# EVE_v0-3.net
KiCad netlist of a schematic drawn in EAGLE
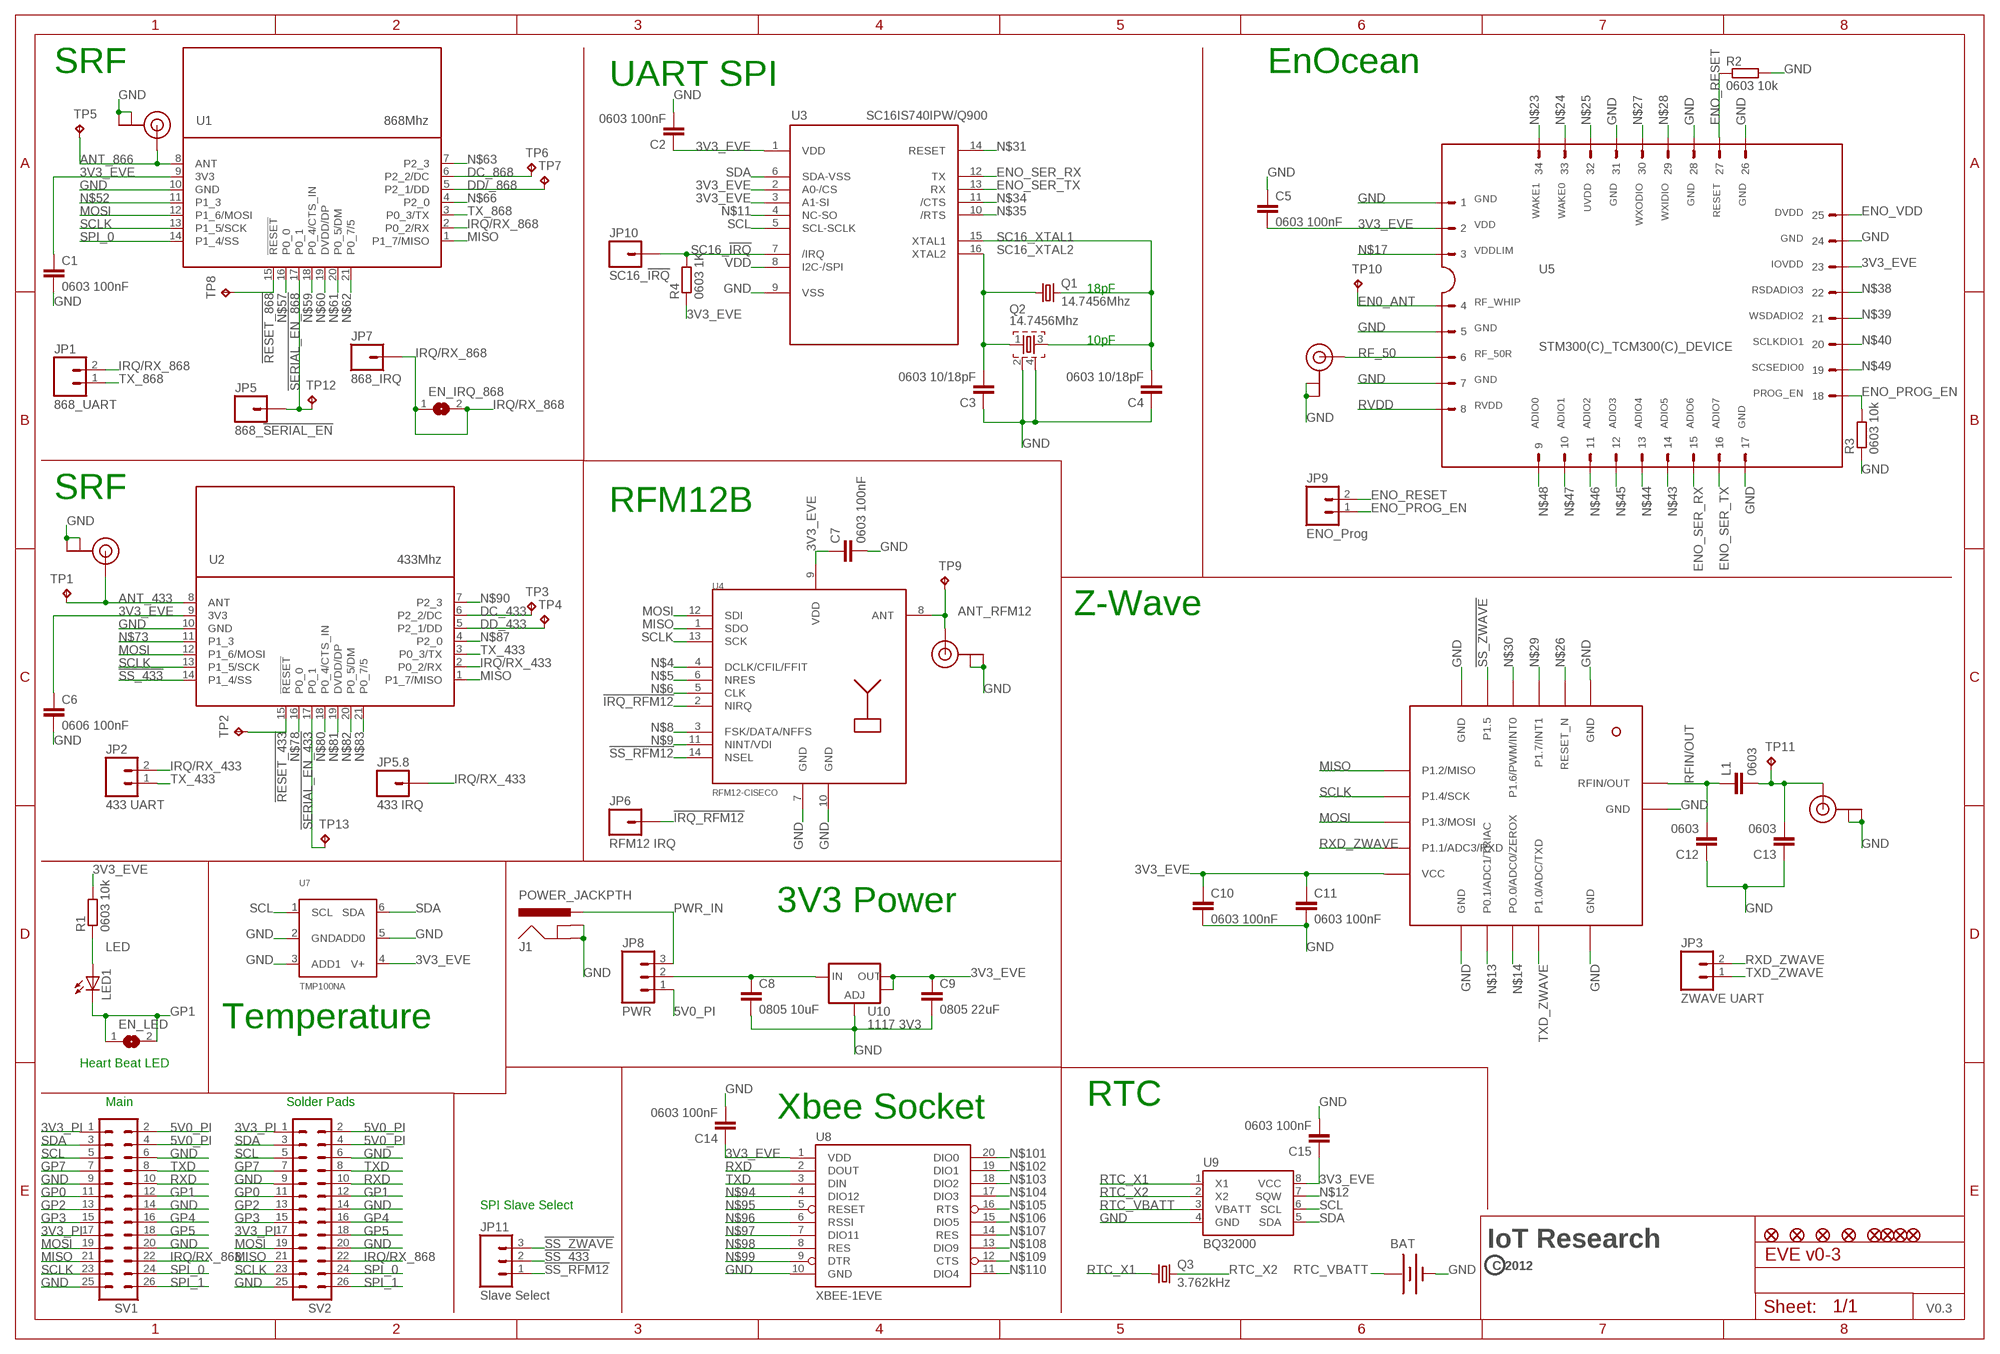
[diagram p0: schematic, sheet 1]

(export (version "E")
  (design (tool "Eeschema 10.0.6"))
  (components
    (comp (ref "BAT")
      (value "BATTERY12MM-BK-855")
      (footprint "eagle-import:BATTCON_12MM-BK-885")
      (libsource (lib "eagle-import") (part "BATTERY12MM-BK-855"))
    )
    (comp (ref "C1")
      (value "0603 100nF")
      (footprint "eagle-import:C0603K-SMALL")
      (libsource (lib "eagle-import") (part "C-EUC0603K-SMALL"))
    )
    (comp (ref "C2")
      (value "0603 100nF")
      (footprint "eagle-import:C0603K-SMALL")
      (libsource (lib "eagle-import") (part "C-EUC0603K-SMALL"))
    )
    (comp (ref "C3")
      (value "0603 10/18pF")
      (footprint "eagle-import:C0603K-SMALL")
      (libsource (lib "eagle-import") (part "C-EUC0603K-SMALL"))
    )
    (comp (ref "C4")
      (value "0603 10/18pF")
      (footprint "eagle-import:C0603K-SMALL")
      (libsource (lib "eagle-import") (part "C-EUC0603K-SMALL"))
    )
    (comp (ref "C5")
      (value "0603 100nF")
      (footprint "eagle-import:C0603K-SMALL")
      (libsource (lib "eagle-import") (part "C-EUC0603K-SMALL"))
    )
    (comp (ref "C6")
      (value "0606 100nF")
      (footprint "eagle-import:C0603K-SMALL")
      (libsource (lib "eagle-import") (part "C-EUC0603K-SMALL"))
    )
    (comp (ref "C7")
      (value "0603 100nF")
      (footprint "eagle-import:C0603K-SMALL")
      (libsource (lib "eagle-import") (part "C-EUC0603K-SMALL"))
    )
    (comp (ref "C8")
      (value "0805 10uF")
      (footprint "eagle-import:C0805")
      (libsource (lib "eagle-import") (part "C-EUC0805"))
    )
    (comp (ref "C9")
      (value "0805 22uF")
      (footprint "eagle-import:C0805")
      (libsource (lib "eagle-import") (part "C-EUC0805"))
    )
    (comp (ref "C10")
      (value "0603 100nF")
      (footprint "eagle-import:C0603K-SMALL")
      (libsource (lib "eagle-import") (part "C-EUC0603K-SMALL"))
    )
    (comp (ref "C11")
      (value "0603 100nF")
      (footprint "eagle-import:C0603K-SMALL")
      (libsource (lib "eagle-import") (part "C-EUC0603K-SMALL"))
    )
    (comp (ref "C12")
      (value "0603")
      (footprint "eagle-import:C0603K-SMALL")
      (libsource (lib "eagle-import") (part "C-EUC0603K-SMALL"))
    )
    (comp (ref "C13")
      (value "0603")
      (footprint "eagle-import:C0603K-SMALL")
      (libsource (lib "eagle-import") (part "C-EUC0603K-SMALL"))
    )
    (comp (ref "C14")
      (value "0603 100nF")
      (footprint "eagle-import:C0603K-SMALL")
      (libsource (lib "eagle-import") (part "C-EUC0603K-SMALL"))
    )
    (comp (ref "C15")
      (value "0603 100nF")
      (footprint "eagle-import:C0603K-SMALL")
      (libsource (lib "eagle-import") (part "C-EUC0603K-SMALL"))
    )
    (comp (ref "EN_IRQ_868")
      (value "SJ")
      (footprint "eagle-import:SJ")
      (libsource (lib "eagle-import") (part "SJ"))
    )
    (comp (ref "EN_LED")
      (value "SJ")
      (footprint "eagle-import:SJ")
      (libsource (lib "eagle-import") (part "SJ"))
    )
    (comp (ref "J1")
      (value "POWER_JACKPTH")
      (footprint "eagle-import:POWER_JACK_PTH")
      (libsource (lib "eagle-import") (part "POWER_JACKPTH"))
    )
    (comp (ref "JP1")
      (value "868_UART")
      (footprint "eagle-import:1X02_NO_SILK")
      (libsource (lib "eagle-import") (part "M021X02_NO_SILK"))
    )
    (comp (ref "JP2")
      (value "433 UART")
      (footprint "eagle-import:1X02_NO_SILK")
      (libsource (lib "eagle-import") (part "M021X02_NO_SILK"))
    )
    (comp (ref "JP3")
      (value "ZWAVE UART")
      (footprint "eagle-import:1X02_NO_SILK")
      (libsource (lib "eagle-import") (part "M021X02_NO_SILK"))
    )
    (comp (ref "JP4")
      (value "FIDUCIAL1X2-STOP")
      (footprint "eagle-import:FIDUCIAL-1X2-STOP")
      (libsource (lib "eagle-import") (part "FIDUCIAL1X2-STOP"))
    )
    (comp (ref "JP5")
      (value "868_!SERIAL_EN")
      (footprint "eagle-import:1X01NS")
      (libsource (lib "eagle-import") (part "M01SMDNS"))
    )
    (comp (ref "JP5.8")
      (value "433 IRQ")
      (footprint "eagle-import:1X01NS")
      (libsource (lib "eagle-import") (part "M01SMDNS"))
    )
    (comp (ref "JP6")
      (value "RFM12 IRQ")
      (footprint "eagle-import:1X01NS")
      (libsource (lib "eagle-import") (part "M01SMDNS"))
    )
    (comp (ref "JP7")
      (value "868_IRQ")
      (footprint "eagle-import:1X01NS")
      (libsource (lib "eagle-import") (part "M01SMDNS"))
    )
    (comp (ref "JP8")
      (value "PWR")
      (footprint "eagle-import:1X03_NO_SILK")
      (libsource (lib "eagle-import") (part "M031X03_NO_SILK"))
    )
    (comp (ref "JP9")
      (value "ENO_Prog")
      (footprint "eagle-import:1X02_NO_SILK")
      (libsource (lib "eagle-import") (part "M021X02_NO_SILK"))
    )
    (comp (ref "JP10")
      (value "SC16_!IRQ")
      (footprint "eagle-import:1X01NS")
      (libsource (lib "eagle-import") (part "M01SMDNS"))
    )
    (comp (ref "JP11")
      (value "Slave Select")
      (footprint "eagle-import:1X03_NO_SILK")
      (libsource (lib "eagle-import") (part "M031X03_NO_SILK"))
    )
    (comp (ref "JP12")
      (value "FIDUCIAL1X2-STOP")
      (footprint "eagle-import:FIDUCIAL-1X2-STOP")
      (libsource (lib "eagle-import") (part "FIDUCIAL1X2-STOP"))
    )
    (comp (ref "JP13")
      (value "FIDUCIAL1X2-STOP")
      (footprint "eagle-import:FIDUCIAL-1X2-STOP")
      (libsource (lib "eagle-import") (part "FIDUCIAL1X2-STOP"))
    )
    (comp (ref "JP14")
      (value "FIDUCIAL1X2-STOP")
      (footprint "eagle-import:FIDUCIAL-1X2-STOP")
      (libsource (lib "eagle-import") (part "FIDUCIAL1X2-STOP"))
    )
    (comp (ref "JP15")
      (value "FIDUCIAL1X2-STOP")
      (footprint "eagle-import:FIDUCIAL-1X2-STOP")
      (libsource (lib "eagle-import") (part "FIDUCIAL1X2-STOP"))
    )
    (comp (ref "JP16")
      (value "FIDUCIAL1X2-STOP")
      (footprint "eagle-import:FIDUCIAL-1X2-STOP")
      (libsource (lib "eagle-import") (part "FIDUCIAL1X2-STOP"))
    )
    (comp (ref "JP17")
      (value "FIDUCIAL1X2-STOP")
      (footprint "eagle-import:FIDUCIAL-1X2-STOP")
      (libsource (lib "eagle-import") (part "FIDUCIAL1X2-STOP"))
    )
    (comp (ref "JP18")
      (value "FIDUCIAL1X2-STOP")
      (footprint "eagle-import:FIDUCIAL-1X2-STOP")
      (libsource (lib "eagle-import") (part "FIDUCIAL1X2-STOP"))
    )
    (comp (ref "L1")
      (value "0603")
      (footprint "eagle-import:C0603K-SMALL")
      (libsource (lib "eagle-import") (part "C-EUC0603K-SMALL"))
    )
    (comp (ref "LED1")
      (value "LEDREVERSE")
      (footprint "eagle-import:LED-REVERSE")
      (libsource (lib "eagle-import") (part "LEDREVERSE"))
    )
    (comp (ref "Q1")
      (value "14.7456Mhz")
      (footprint "eagle-import:CRYSTAL-SMD-10.5X4.8-2PIN")
      (libsource (lib "eagle-import") (part "CRYSTAL10.5X4.8"))
    )
    (comp (ref "Q2")
      (value "14.7456Mhz")
      (footprint "eagle-import:CRYSTAL-SMD-ABM8G")
      (libsource (lib "eagle-import") (part "CRYSTAL-SMD"))
    )
    (comp (ref "Q3")
      (value "3.762kHz")
      (footprint "eagle-import:MC-306")
      (fields (field (name "MPN") "MC-306 60.0KHZ  100PPM ,12.5PF"))
      (libsource (lib "eagle-import") (part "MC-306"))
    )
    (comp (ref "R1")
      (value "0603 10k")
      (footprint "eagle-import:C0603K-SMALL")
      (libsource (lib "eagle-import") (part "R-EU_0603K-SMALL"))
    )
    (comp (ref "R2")
      (value "0603 10k")
      (footprint "eagle-import:C0603K-SMALL")
      (libsource (lib "eagle-import") (part "R-EU_0603K-SMALL"))
    )
    (comp (ref "R3")
      (value "0603 10k")
      (footprint "eagle-import:C0603K-SMALL")
      (libsource (lib "eagle-import") (part "R-EU_0603K-SMALL"))
    )
    (comp (ref "R4")
      (value "0603 1K")
      (footprint "eagle-import:C0603K-SMALL")
      (libsource (lib "eagle-import") (part "R-EU_0603K-SMALL"))
    )
    (comp (ref "SV1")
      (value "MA13-2-NO-SILK")
      (footprint "eagle-import:MA13-2-NS")
      (libsource (lib "eagle-import") (part "MA13-2-NO-SILK"))
    )
    (comp (ref "SV2")
      (value "MA13-2")
      (footprint "eagle-import:MA13-2")
      (libsource (lib "eagle-import") (part "MA13-2"))
    )
    (comp (ref "TP1")
      (value "TPPAD1-13")
      (footprint "eagle-import:P1-13")
      (libsource (lib "eagle-import") (part "TPPAD1-13"))
    )
    (comp (ref "TP2")
      (value "TPB1,27")
      (footprint "eagle-import:B1,27")
      (libsource (lib "eagle-import") (part "TPB1,27"))
    )
    (comp (ref "TP3")
      (value "TPB1,27")
      (footprint "eagle-import:B1,27")
      (libsource (lib "eagle-import") (part "TPB1,27"))
    )
    (comp (ref "TP4")
      (value "TPB1,27")
      (footprint "eagle-import:B1,27")
      (libsource (lib "eagle-import") (part "TPB1,27"))
    )
    (comp (ref "TP5")
      (value "TPPAD1-13")
      (footprint "eagle-import:P1-13")
      (libsource (lib "eagle-import") (part "TPPAD1-13"))
    )
    (comp (ref "TP6")
      (value "TPB1,27")
      (footprint "eagle-import:B1,27")
      (libsource (lib "eagle-import") (part "TPB1,27"))
    )
    (comp (ref "TP7")
      (value "TPB1,27")
      (footprint "eagle-import:B1,27")
      (libsource (lib "eagle-import") (part "TPB1,27"))
    )
    (comp (ref "TP8")
      (value "TPB1,27")
      (footprint "eagle-import:B1,27")
      (libsource (lib "eagle-import") (part "TPB1,27"))
    )
    (comp (ref "TP9")
      (value "TPPAD1-13")
      (footprint "eagle-import:P1-13")
      (libsource (lib "eagle-import") (part "TPPAD1-13"))
    )
    (comp (ref "TP10")
      (value "TPPAD1-13")
      (footprint "eagle-import:P1-13")
      (libsource (lib "eagle-import") (part "TPPAD1-13"))
    )
    (comp (ref "TP11")
      (value "TPPAD1-13")
      (footprint "eagle-import:P1-13")
      (libsource (lib "eagle-import") (part "TPPAD1-13"))
    )
    (comp (ref "TP12")
      (value "TPB1,27")
      (footprint "eagle-import:B1,27")
      (libsource (lib "eagle-import") (part "TPB1,27"))
    )
    (comp (ref "TP13")
      (value "TPB1,27")
      (footprint "eagle-import:B1,27")
      (libsource (lib "eagle-import") (part "TPB1,27"))
    )
    (comp (ref "U1")
      (value "868Mhz")
      (footprint "eagle-import:SRF-LANDING")
      (libsource (lib "eagle-import") (part "SRFSRF-LANDING"))
    )
    (comp (ref "U2")
      (value "433Mhz")
      (footprint "eagle-import:SRF-LANDING-NO-ANT")
      (libsource (lib "eagle-import") (part "SRFSRF-LANDING-NO-ANT"))
    )
    (comp (ref "U3")
      (value "SC16IS740IPW/Q900")
      (footprint "eagle-import:TSSOP-16")
      (libsource (lib "eagle-import") (part "SC16IS740IPW/Q900"))
    )
    (comp (ref "U4")
      (value "RFM12-CISECO")
      (footprint "eagle-import:RFM-CISECO")
      (libsource (lib "eagle-import") (part "RFM12-CISECO"))
    )
    (comp (ref "U5")
      (value "STM300(C)_TCM300(C)_DEVICE")
      (footprint "eagle-import:STM300(C)_TCM300(C)_FOOTPRINT")
      (libsource (lib "eagle-import") (part "STM300(C)_TCM300(C)_DEVICE"))
    )
    (comp (ref "U6")
      (value "ZWAVE-ZM3102N")
      (footprint "eagle-import:ZWAVE-ZM3102N")
      (libsource (lib "eagle-import") (part "ZWAVE-ZM3102N"))
    )
    (comp (ref "U7")
      (value "TMP100NA")
      (footprint "eagle-import:SOT-23-6")
      (libsource (lib "eagle-import") (part "TMP100{dblquote}"))
    )
    (comp (ref "U8")
      (value "XBEE-1EVE")
      (footprint "eagle-import:XBEE-EVE")
      (libsource (lib "eagle-import") (part "XBEE-1EVE"))
    )
    (comp (ref "U9")
      (value "BQ32000")
      (footprint "eagle-import:SO08")
      (libsource (lib "eagle-import") (part "DS1307SO8"))
    )
    (comp (ref "U10")
      (value "1117 3V3")
      (footprint "eagle-import:SOT223")
      (libsource (lib "eagle-import") (part "V_REG_LM1117SOT223"))
    )
    (comp (ref "U11")
      (value "U.FL 868")
      (footprint "eagle-import:U.FL")
      (libsource (lib "eagle-import") (part "U.FL"))
    )
    (comp (ref "U12")
      (value "U.FL EnOcean")
      (footprint "eagle-import:U.FL")
      (libsource (lib "eagle-import") (part "U.FL"))
    )
    (comp (ref "U13")
      (value "U.FL 433")
      (footprint "eagle-import:U.FL")
      (libsource (lib "eagle-import") (part "U.FL"))
    )
    (comp (ref "U14")
      (value "U.FL RFM12B")
      (footprint "eagle-import:U.FL")
      (libsource (lib "eagle-import") (part "U.FL"))
    )
    (comp (ref "U15")
      (value "U.FL Z-Wave")
      (footprint "eagle-import:U.FL")
      (libsource (lib "eagle-import") (part "U.FL"))
    )
  )
  (nets
    (net (code "1") (name "/3V3_EVE") (class "Default")
      (node (ref "C1") (pin "1") (pinfunction "1_1") (pintype "passive"))
      (node (ref "C10") (pin "1") (pinfunction "1_1") (pintype "passive"))
      (node (ref "C11") (pin "1") (pinfunction "1_1") (pintype "passive"))
      (node (ref "C14") (pin "1") (pinfunction "1_1") (pintype "passive"))
      (node (ref "C15") (pin "1") (pinfunction "1_1") (pintype "passive"))
      (node (ref "C2") (pin "1") (pinfunction "1_1") (pintype "passive"))
      (node (ref "C5") (pin "2") (pinfunction "2_2") (pintype "passive"))
      (node (ref "C6") (pin "1") (pinfunction "1_1") (pintype "passive"))
      (node (ref "C7") (pin "1") (pinfunction "1_1") (pintype "passive"))
      (node (ref "C9") (pin "1") (pinfunction "1_1") (pintype "passive"))
      (node (ref "R1") (pin "2") (pinfunction "2_2") (pintype "passive"))
      (node (ref "R4") (pin "1") (pinfunction "1_1") (pintype "passive"))
      (node (ref "U1") (pin "9") (pinfunction "3V3_9") (pintype "power_in"))
      (node (ref "U10") (pin "2") (pinfunction "OUT_2") (pintype "output"))
      (node (ref "U10") (pin "4") (pinfunction "OUT_4") (pintype "output"))
      (node (ref "U2") (pin "9") (pinfunction "3V3_9") (pintype "power_in"))
      (node (ref "U3") (pin "1") (pinfunction "VDD_1") (pintype "bidirectional"))
      (node (ref "U3") (pin "2") (pinfunction "A0-/CS_2") (pintype "bidirectional"))
      (node (ref "U3") (pin "3") (pinfunction "A1-SI_3") (pintype "bidirectional"))
      (node (ref "U4") (pin "9") (pinfunction "VDD_9") (pintype "power_in"))
      (node (ref "U5") (pin "2") (pinfunction "2_2") (pintype "passive"))
      (node (ref "U5") (pin "23") (pinfunction "23_23") (pintype "passive"))
      (node (ref "U6") (pin "11") (pinfunction "VCC_11") (pintype "bidirectional"))
      (node (ref "U7") (pin "4") (pinfunction "V+_4") (pintype "bidirectional"))
      (node (ref "U8") (pin "1") (pinfunction "VDD_1") (pintype "power_in"))
      (node (ref "U9") (pin "8") (pinfunction "VCC_8") (pintype "bidirectional"))
    )
    (net (code "2") (name "/3V3_PI") (class "Default")
      (node (ref "SV1") (pin "1") (pinfunction "1_1") (pintype "passive"))
      (node (ref "SV1") (pin "17") (pinfunction "17_17") (pintype "passive"))
      (node (ref "SV2") (pin "1") (pinfunction "1_1") (pintype "passive"))
      (node (ref "SV2") (pin "17") (pinfunction "17_17") (pintype "passive"))
    )
    (net (code "3") (name "/5V0_PI") (class "Default")
      (node (ref "JP8") (pin "1") (pinfunction "1_1") (pintype "passive"))
      (node (ref "SV1") (pin "2") (pinfunction "2_2") (pintype "passive"))
      (node (ref "SV1") (pin "4") (pinfunction "4_4") (pintype "passive"))
      (node (ref "SV2") (pin "2") (pinfunction "2_2") (pintype "passive"))
      (node (ref "SV2") (pin "4") (pinfunction "4_4") (pintype "passive"))
    )
    (net (code "4") (name "/ANT_433") (class "Default")
      (node (ref "TP1") (pin "TP") (pinfunction "TP_TP") (pintype "input"))
      (node (ref "U13") (pin "P$3") (pinfunction "SIGNAL_P$3") (pintype "bidirectional"))
      (node (ref "U2") (pin "8") (pinfunction "ANT_8") (pintype "output"))
    )
    (net (code "5") (name "/ANT_866") (class "Default")
      (node (ref "TP5") (pin "TP") (pinfunction "TP_TP") (pintype "input"))
      (node (ref "U1") (pin "8") (pinfunction "ANT_8") (pintype "output"))
      (node (ref "U11") (pin "P$3") (pinfunction "SIGNAL_P$3") (pintype "bidirectional"))
    )
    (net (code "6") (name "/ANT_RFM12") (class "Default")
      (node (ref "TP9") (pin "TP") (pinfunction "TP_TP") (pintype "input"))
      (node (ref "U14") (pin "P$3") (pinfunction "SIGNAL_P$3") (pintype "bidirectional"))
      (node (ref "U4") (pin "8") (pinfunction "ANT_8") (pintype "output"))
    )
    (net (code "7") (name "/DC_433") (class "Default")
      (node (ref "TP3") (pin "TP") (pinfunction "TP_TP") (pintype "input"))
      (node (ref "U2") (pin "6") (pinfunction "P2_2/DC_6") (pintype "bidirectional"))
    )
    (net (code "8") (name "/DC_868") (class "Default")
      (node (ref "TP6") (pin "TP") (pinfunction "TP_TP") (pintype "input"))
      (node (ref "U1") (pin "6") (pinfunction "P2_2/DC_6") (pintype "bidirectional"))
    )
    (net (code "9") (name "/DD_433") (class "Default")
      (node (ref "TP4") (pin "TP") (pinfunction "TP_TP") (pintype "input"))
      (node (ref "U2") (pin "5") (pinfunction "P2_1/DD_5") (pintype "bidirectional"))
    )
    (net (code "10") (name "/DD{slash}_868") (class "Default")
      (node (ref "TP7") (pin "TP") (pinfunction "TP_TP") (pintype "input"))
      (node (ref "U1") (pin "5") (pinfunction "P2_1/DD_5") (pintype "bidirectional"))
    )
    (net (code "11") (name "/EN0_ANT") (class "Default")
      (node (ref "TP10") (pin "TP") (pinfunction "TP_TP") (pintype "input"))
      (node (ref "U5") (pin "4") (pinfunction "4_4") (pintype "passive"))
    )
    (net (code "12") (name "/ENO_PROG_EN") (class "Default")
      (node (ref "JP9") (pin "1") (pinfunction "1_1") (pintype "passive"))
      (node (ref "R3") (pin "2") (pinfunction "2_2") (pintype "passive"))
      (node (ref "U5") (pin "18") (pinfunction "18_18") (pintype "passive"))
    )
    (net (code "13") (name "/ENO_RESET") (class "Default")
      (node (ref "JP9") (pin "2") (pinfunction "2_2") (pintype "passive"))
      (node (ref "R2") (pin "1") (pinfunction "1_1") (pintype "passive"))
      (node (ref "U5") (pin "27") (pinfunction "27_27") (pintype "passive"))
    )
    (net (code "14") (name "/ENO_SER_RX") (class "Default")
      (node (ref "U3") (pin "12") (pinfunction "TX_12") (pintype "bidirectional"))
      (node (ref "U5") (pin "15") (pinfunction "15_15") (pintype "passive"))
    )
    (net (code "15") (name "/ENO_SER_TX") (class "Default")
      (node (ref "U3") (pin "13") (pinfunction "RX_13") (pintype "bidirectional"))
      (node (ref "U5") (pin "16") (pinfunction "16_16") (pintype "passive"))
    )
    (net (code "16") (name "/ENO_VDD") (class "Default")
      (node (ref "U5") (pin "25") (pinfunction "25_25") (pintype "passive"))
    )
    (net (code "17") (name "/GND") (class "Default")
      (node (ref "BAT") (pin "GND") (pinfunction "-_GND") (pintype "power_in"))
      (node (ref "C1") (pin "2") (pinfunction "2_2") (pintype "passive"))
      (node (ref "C10") (pin "2") (pinfunction "2_2") (pintype "passive"))
      (node (ref "C11") (pin "2") (pinfunction "2_2") (pintype "passive"))
      (node (ref "C12") (pin "1") (pinfunction "1_1") (pintype "passive"))
      (node (ref "C13") (pin "1") (pinfunction "1_1") (pintype "passive"))
      (node (ref "C14") (pin "2") (pinfunction "2_2") (pintype "passive"))
      (node (ref "C15") (pin "2") (pinfunction "2_2") (pintype "passive"))
      (node (ref "C2") (pin "2") (pinfunction "2_2") (pintype "passive"))
      (node (ref "C3") (pin "1") (pinfunction "1_1") (pintype "passive"))
      (node (ref "C4") (pin "1") (pinfunction "1_1") (pintype "passive"))
      (node (ref "C5") (pin "1") (pinfunction "1_1") (pintype "passive"))
      (node (ref "C6") (pin "2") (pinfunction "2_2") (pintype "passive"))
      (node (ref "C7") (pin "2") (pinfunction "2_2") (pintype "passive"))
      (node (ref "C8") (pin "2") (pinfunction "2_2") (pintype "passive"))
      (node (ref "C9") (pin "2") (pinfunction "2_2") (pintype "passive"))
      (node (ref "J1") (pin "GND") (pinfunction "GND_GND") (pintype "bidirectional"))
      (node (ref "J1") (pin "GNDBREAK") (pinfunction "GNDBREAK_GNDBREAK") (pintype "bidirectional"))
      (node (ref "Q2") (pin "2") (pinfunction "2_2") (pintype "passive"))
      (node (ref "Q2") (pin "4") (pinfunction "4_4") (pintype "passive"))
      (node (ref "R2") (pin "2") (pinfunction "2_2") (pintype "passive"))
      (node (ref "R3") (pin "1") (pinfunction "1_1") (pintype "passive"))
      (node (ref "SV1") (pin "14") (pinfunction "14_14") (pintype "passive"))
      (node (ref "SV1") (pin "20") (pinfunction "20_20") (pintype "passive"))
      (node (ref "SV1") (pin "25") (pinfunction "25_25") (pintype "passive"))
      (node (ref "SV1") (pin "6") (pinfunction "6_6") (pintype "passive"))
      (node (ref "SV1") (pin "9") (pinfunction "9_9") (pintype "passive"))
      (node (ref "SV2") (pin "14") (pinfunction "14_14") (pintype "passive"))
      (node (ref "SV2") (pin "20") (pinfunction "20_20") (pintype "passive"))
      (node (ref "SV2") (pin "25") (pinfunction "25_25") (pintype "passive"))
      (node (ref "SV2") (pin "6") (pinfunction "6_6") (pintype "passive"))
      (node (ref "SV2") (pin "9") (pinfunction "9_9") (pintype "passive"))
      (node (ref "U1") (pin "10") (pinfunction "GND_10") (pintype "power_in"))
      (node (ref "U10") (pin "1") (pinfunction "ADJ_1") (pintype "input"))
      (node (ref "U11") (pin "P$1") (pinfunction "GND_P$1") (pintype "bidirectional"))
      (node (ref "U11") (pin "P$2") (pinfunction "GND_P$2") (pintype "bidirectional"))
      (node (ref "U12") (pin "P$1") (pinfunction "GND_P$1") (pintype "bidirectional"))
      (node (ref "U12") (pin "P$2") (pinfunction "GND_P$2") (pintype "bidirectional"))
      (node (ref "U13") (pin "P$1") (pinfunction "GND_P$1") (pintype "bidirectional"))
      (node (ref "U13") (pin "P$2") (pinfunction "GND_P$2") (pintype "bidirectional"))
      (node (ref "U14") (pin "P$1") (pinfunction "GND_P$1") (pintype "bidirectional"))
      (node (ref "U14") (pin "P$2") (pinfunction "GND_P$2") (pintype "bidirectional"))
      (node (ref "U15") (pin "P$1") (pinfunction "GND_P$1") (pintype "bidirectional"))
      (node (ref "U15") (pin "P$2") (pinfunction "GND_P$2") (pintype "bidirectional"))
      (node (ref "U2") (pin "10") (pinfunction "GND_10") (pintype "power_in"))
      (node (ref "U3") (pin "9") (pinfunction "VSS_9") (pintype "bidirectional"))
      (node (ref "U4") (pin "10") (pinfunction "GND_10") (pintype "power_in"))
      (node (ref "U4") (pin "7") (pinfunction "GND_7") (pintype "power_in"))
      (node (ref "U5") (pin "1") (pinfunction "1_1") (pintype "passive"))
      (node (ref "U5") (pin "17") (pinfunction "17_17") (pintype "passive"))
      (node (ref "U5") (pin "24") (pinfunction "24_24") (pintype "passive"))
      (node (ref "U5") (pin "26") (pinfunction "26_26") (pintype "passive"))
      (node (ref "U5") (pin "28") (pinfunction "28_28") (pintype "passive"))
      (node (ref "U5") (pin "31") (pinfunction "31_31") (pintype "passive"))
      (node (ref "U5") (pin "5") (pinfunction "5_5") (pintype "passive"))
      (node (ref "U5") (pin "7") (pinfunction "7_7") (pintype "passive"))
      (node (ref "U6") (pin "1") (pinfunction "GND_1") (pintype "bidirectional"))
      (node (ref "U6") (pin "12") (pinfunction "GND_12") (pintype "bidirectional"))
      (node (ref "U6") (pin "16") (pinfunction "GND_16") (pintype "bidirectional"))
      (node (ref "U6") (pin "17") (pinfunction "GND_17") (pintype "bidirectional"))
      (node (ref "U6") (pin "6") (pinfunction "GND_6") (pintype "bidirectional"))
      (node (ref "U7") (pin "2") (pinfunction "GND_2") (pintype "bidirectional"))
      (node (ref "U7") (pin "3") (pinfunction "ADD1_3") (pintype "bidirectional"))
      (node (ref "U7") (pin "5") (pinfunction "ADD0_5") (pintype "bidirectional"))
      (node (ref "U8") (pin "10") (pinfunction "GND_10") (pintype "power_in"))
      (node (ref "U9") (pin "4") (pinfunction "GND_4") (pintype "bidirectional"))
    )
    (net (code "18") (name "/GP0") (class "Default")
      (node (ref "SV1") (pin "11") (pinfunction "11_11") (pintype "passive"))
      (node (ref "SV2") (pin "11") (pinfunction "11_11") (pintype "passive"))
    )
    (net (code "19") (name "/GP1") (class "Default")
      (node (ref "EN_LED") (pin "1") (pinfunction "1_1") (pintype "passive"))
      (node (ref "EN_LED") (pin "2") (pinfunction "2_2") (pintype "passive"))
      (node (ref "LED1") (pin "C") (pinfunction "C_C") (pintype "passive"))
      (node (ref "SV1") (pin "12") (pinfunction "12_12") (pintype "passive"))
      (node (ref "SV2") (pin "12") (pinfunction "12_12") (pintype "passive"))
    )
    (net (code "20") (name "/GP2") (class "Default")
      (node (ref "SV1") (pin "13") (pinfunction "13_13") (pintype "passive"))
      (node (ref "SV2") (pin "13") (pinfunction "13_13") (pintype "passive"))
    )
    (net (code "21") (name "/GP3") (class "Default")
      (node (ref "SV1") (pin "15") (pinfunction "15_15") (pintype "passive"))
      (node (ref "SV2") (pin "15") (pinfunction "15_15") (pintype "passive"))
    )
    (net (code "22") (name "/GP4") (class "Default")
      (node (ref "SV1") (pin "16") (pinfunction "16_16") (pintype "passive"))
      (node (ref "SV2") (pin "16") (pinfunction "16_16") (pintype "passive"))
    )
    (net (code "23") (name "/GP5") (class "Default")
      (node (ref "SV1") (pin "18") (pinfunction "18_18") (pintype "passive"))
      (node (ref "SV2") (pin "18") (pinfunction "18_18") (pintype "passive"))
    )
    (net (code "24") (name "/GP7") (class "Default")
      (node (ref "SV1") (pin "7") (pinfunction "7_7") (pintype "passive"))
      (node (ref "SV2") (pin "7") (pinfunction "7_7") (pintype "passive"))
    )
    (net (code "25") (name "/IRQ{slash}RX_433") (class "Default")
      (node (ref "JP2") (pin "2") (pinfunction "2_2") (pintype "passive"))
      (node (ref "JP5.8") (pin "1") (pinfunction "1_1") (pintype "passive"))
      (node (ref "U2") (pin "2") (pinfunction "P0_2/RX_2") (pintype "bidirectional"))
    )
    (net (code "26") (name "/IRQ{slash}RX_868") (class "Default")
      (node (ref "EN_IRQ_868") (pin "1") (pinfunction "1_1") (pintype "passive"))
      (node (ref "EN_IRQ_868") (pin "2") (pinfunction "2_2") (pintype "passive"))
      (node (ref "JP1") (pin "2") (pinfunction "2_2") (pintype "passive"))
      (node (ref "JP7") (pin "1") (pinfunction "1_1") (pintype "passive"))
      (node (ref "SV1") (pin "22") (pinfunction "22_22") (pintype "passive"))
      (node (ref "SV2") (pin "22") (pinfunction "22_22") (pintype "passive"))
      (node (ref "U1") (pin "2") (pinfunction "P0_2/RX_2") (pintype "bidirectional"))
    )
    (net (code "27") (name "/LED") (class "Default")
      (node (ref "LED1") (pin "A") (pinfunction "A_A") (pintype "passive"))
      (node (ref "R1") (pin "1") (pinfunction "1_1") (pintype "passive"))
    )
    (net (code "28") (name "/MISO") (class "Default")
      (node (ref "SV1") (pin "21") (pinfunction "21_21") (pintype "passive"))
      (node (ref "SV2") (pin "21") (pinfunction "21_21") (pintype "passive"))
      (node (ref "U1") (pin "1") (pinfunction "P1_7/MISO_1") (pintype "bidirectional"))
      (node (ref "U2") (pin "1") (pinfunction "P1_7/MISO_1") (pintype "bidirectional"))
      (node (ref "U4") (pin "1") (pinfunction "SDO_1") (pintype "bidirectional"))
      (node (ref "U6") (pin "7") (pinfunction "P1.2/MISO_7") (pintype "bidirectional"))
    )
    (net (code "29") (name "/MOSI") (class "Default")
      (node (ref "SV1") (pin "19") (pinfunction "19_19") (pintype "passive"))
      (node (ref "SV2") (pin "19") (pinfunction "19_19") (pintype "passive"))
      (node (ref "U1") (pin "12") (pinfunction "P1_6/MOSI_12") (pintype "bidirectional"))
      (node (ref "U2") (pin "12") (pinfunction "P1_6/MOSI_12") (pintype "bidirectional"))
      (node (ref "U4") (pin "12") (pinfunction "SDI_12") (pintype "bidirectional"))
      (node (ref "U6") (pin "9") (pinfunction "P1.3/MOSI_9") (pintype "bidirectional"))
    )
    (net (code "30") (name "/N$4") (class "Default")
      (node (ref "U4") (pin "4") (pinfunction "DCLK/CFIL/FFIT_4") (pintype "bidirectional"))
    )
    (net (code "31") (name "/N$5") (class "Default")
      (node (ref "U4") (pin "6") (pinfunction "NRES_6") (pintype "bidirectional"))
    )
    (net (code "32") (name "/N$6") (class "Default")
      (node (ref "U4") (pin "5") (pinfunction "CLK_5") (pintype "bidirectional"))
    )
    (net (code "33") (name "/N$8") (class "Default")
      (node (ref "U4") (pin "3") (pinfunction "FSK/DATA/NFFS_3") (pintype "bidirectional"))
    )
    (net (code "34") (name "/N$9") (class "Default")
      (node (ref "U4") (pin "11") (pinfunction "NINT/VDI_11") (pintype "bidirectional"))
    )
    (net (code "35") (name "/N$11") (class "Default")
      (node (ref "U3") (pin "4") (pinfunction "NC-SO_4") (pintype "bidirectional"))
    )
    (net (code "36") (name "/N$12") (class "Default")
      (node (ref "U9") (pin "7") (pinfunction "SQW_7") (pintype "bidirectional"))
    )
    (net (code "37") (name "/N$13") (class "Default")
      (node (ref "U6") (pin "13") (pinfunction "P0.1/ADC1/TRIAC_13") (pintype "bidirectional"))
    )
    (net (code "38") (name "/N$14") (class "Default")
      (node (ref "U6") (pin "14") (pinfunction "PO.0/ADC0/ZEROX_14") (pintype "bidirectional"))
    )
    (net (code "39") (name "/N$17") (class "Default")
      (node (ref "U5") (pin "3") (pinfunction "3_3") (pintype "passive"))
    )
    (net (code "40") (name "/N$23") (class "Default")
      (node (ref "U5") (pin "34") (pinfunction "34_34") (pintype "passive"))
    )
    (net (code "41") (name "/N$24") (class "Default")
      (node (ref "U5") (pin "33") (pinfunction "33_33") (pintype "passive"))
    )
    (net (code "42") (name "/N$25") (class "Default")
      (node (ref "U5") (pin "32") (pinfunction "32_32") (pintype "passive"))
    )
    (net (code "43") (name "/N$26") (class "Default")
      (node (ref "U6") (pin "2") (pinfunction "RESET_N_2") (pintype "bidirectional"))
    )
    (net (code "44") (name "/N$27") (class "Default")
      (node (ref "U5") (pin "30") (pinfunction "30_30") (pintype "passive"))
    )
    (net (code "45") (name "/N$28") (class "Default")
      (node (ref "U5") (pin "29") (pinfunction "29_29") (pintype "passive"))
    )
    (net (code "46") (name "/N$29") (class "Default")
      (node (ref "U6") (pin "3") (pinfunction "P1.7/INT1_3") (pintype "bidirectional"))
    )
    (net (code "47") (name "/N$30") (class "Default")
      (node (ref "U6") (pin "4") (pinfunction "P1.6/PWM/INT0_4") (pintype "bidirectional"))
    )
    (net (code "48") (name "/N$31") (class "Default")
      (node (ref "U3") (pin "14") (pinfunction "RESET_14") (pintype "bidirectional"))
    )
    (net (code "49") (name "/N$34") (class "Default")
      (node (ref "U3") (pin "11") (pinfunction "/CTS_11") (pintype "bidirectional"))
    )
    (net (code "50") (name "/N$35") (class "Default")
      (node (ref "U3") (pin "10") (pinfunction "/RTS_10") (pintype "bidirectional"))
    )
    (net (code "51") (name "/N$38") (class "Default")
      (node (ref "U5") (pin "22") (pinfunction "22_22") (pintype "passive"))
    )
    (net (code "52") (name "/N$39") (class "Default")
      (node (ref "U5") (pin "21") (pinfunction "21_21") (pintype "passive"))
    )
    (net (code "53") (name "/N$40") (class "Default")
      (node (ref "U5") (pin "20") (pinfunction "20_20") (pintype "passive"))
    )
    (net (code "54") (name "/N$43") (class "Default")
      (node (ref "U5") (pin "14") (pinfunction "14_14") (pintype "passive"))
    )
    (net (code "55") (name "/N$44") (class "Default")
      (node (ref "U5") (pin "13") (pinfunction "13_13") (pintype "passive"))
    )
    (net (code "56") (name "/N$45") (class "Default")
      (node (ref "U5") (pin "12") (pinfunction "12_12") (pintype "passive"))
    )
    (net (code "57") (name "/N$46") (class "Default")
      (node (ref "U5") (pin "11") (pinfunction "11_11") (pintype "passive"))
    )
    (net (code "58") (name "/N$47") (class "Default")
      (node (ref "U5") (pin "10") (pinfunction "10_10") (pintype "passive"))
    )
    (net (code "59") (name "/N$48") (class "Default")
      (node (ref "U5") (pin "9") (pinfunction "9_9") (pintype "passive"))
    )
    (net (code "60") (name "/N$49") (class "Default")
      (node (ref "U5") (pin "19") (pinfunction "19_19") (pintype "passive"))
    )
    (net (code "61") (name "/N$52") (class "Default")
      (node (ref "U1") (pin "11") (pinfunction "P1_3_11") (pintype "bidirectional"))
    )
    (net (code "62") (name "/N$57") (class "Default")
      (node (ref "U1") (pin "16") (pinfunction "P0_0_16") (pintype "bidirectional"))
    )
    (net (code "63") (name "/N$59") (class "Default")
      (node (ref "U1") (pin "18") (pinfunction "P0_4/CTS_IN_18") (pintype "bidirectional"))
    )
    (net (code "64") (name "/N$60") (class "Default")
      (node (ref "U1") (pin "19") (pinfunction "DVDD/DP_19") (pintype "bidirectional"))
    )
    (net (code "65") (name "/N$61") (class "Default")
      (node (ref "U1") (pin "20") (pinfunction "P0_5/DM_20") (pintype "bidirectional"))
    )
    (net (code "66") (name "/N$62") (class "Default")
      (node (ref "U1") (pin "21") (pinfunction "P0_7/5_21") (pintype "bidirectional"))
    )
    (net (code "67") (name "/N$63") (class "Default")
      (node (ref "U1") (pin "7") (pinfunction "P2_3_7") (pintype "bidirectional"))
    )
    (net (code "68") (name "/N$66") (class "Default")
      (node (ref "U1") (pin "4") (pinfunction "P2_0_4") (pintype "bidirectional"))
    )
    (net (code "69") (name "/N$73") (class "Default")
      (node (ref "U2") (pin "11") (pinfunction "P1_3_11") (pintype "bidirectional"))
    )
    (net (code "70") (name "/N$78") (class "Default")
      (node (ref "U2") (pin "16") (pinfunction "P0_0_16") (pintype "bidirectional"))
    )
    (net (code "71") (name "/N$80") (class "Default")
      (node (ref "U2") (pin "18") (pinfunction "P0_4/CTS_IN_18") (pintype "bidirectional"))
    )
    (net (code "72") (name "/N$81") (class "Default")
      (node (ref "U2") (pin "19") (pinfunction "DVDD/DP_19") (pintype "bidirectional"))
    )
    (net (code "73") (name "/N$82") (class "Default")
      (node (ref "U2") (pin "20") (pinfunction "P0_5/DM_20") (pintype "bidirectional"))
    )
    (net (code "74") (name "/N$83") (class "Default")
      (node (ref "U2") (pin "21") (pinfunction "P0_7/5_21") (pintype "bidirectional"))
    )
    (net (code "75") (name "/N$87") (class "Default")
      (node (ref "U2") (pin "4") (pinfunction "P2_0_4") (pintype "bidirectional"))
    )
    (net (code "76") (name "/N$90") (class "Default")
      (node (ref "U2") (pin "7") (pinfunction "P2_3_7") (pintype "bidirectional"))
    )
    (net (code "77") (name "/N$94") (class "Default")
      (node (ref "U8") (pin "4") (pinfunction "DIO12_4") (pintype "bidirectional"))
    )
    (net (code "78") (name "/N$95") (class "Default")
      (node (ref "U8") (pin "5") (pinfunction "RESET_5") (pintype "input"))
    )
    (net (code "79") (name "/N$96") (class "Default")
      (node (ref "U8") (pin "6") (pinfunction "RSSI_6") (pintype "bidirectional"))
    )
    (net (code "80") (name "/N$97") (class "Default")
      (node (ref "U8") (pin "7") (pinfunction "DIO11_7") (pintype "bidirectional"))
    )
    (net (code "81") (name "/N$98") (class "Default")
      (node (ref "U8") (pin "8") (pinfunction "RES_8") (pintype "bidirectional"))
    )
    (net (code "82") (name "/N$99") (class "Default")
      (node (ref "U8") (pin "9") (pinfunction "DTR_9") (pintype "bidirectional"))
    )
    (net (code "83") (name "/N$101") (class "Default")
      (node (ref "U8") (pin "20") (pinfunction "DIO0_20") (pintype "bidirectional"))
    )
    (net (code "84") (name "/N$102") (class "Default")
      (node (ref "U8") (pin "19") (pinfunction "DIO1_19") (pintype "bidirectional"))
    )
    (net (code "85") (name "/N$103") (class "Default")
      (node (ref "U8") (pin "18") (pinfunction "DIO2_18") (pintype "bidirectional"))
    )
    (net (code "86") (name "/N$104") (class "Default")
      (node (ref "U8") (pin "17") (pinfunction "DIO3_17") (pintype "bidirectional"))
    )
    (net (code "87") (name "/N$105") (class "Default")
      (node (ref "U8") (pin "16") (pinfunction "RTS_16") (pintype "input"))
    )
    (net (code "88") (name "/N$106") (class "Default")
      (node (ref "U8") (pin "15") (pinfunction "DIO5_15") (pintype "bidirectional"))
    )
    (net (code "89") (name "/N$107") (class "Default")
      (node (ref "U8") (pin "14") (pinfunction "RES_14") (pintype "bidirectional"))
    )
    (net (code "90") (name "/N$108") (class "Default")
      (node (ref "U8") (pin "13") (pinfunction "DIO9_13") (pintype "bidirectional"))
    )
    (net (code "91") (name "/N$109") (class "Default")
      (node (ref "U8") (pin "12") (pinfunction "CTS_12") (pintype "output"))
    )
    (net (code "92") (name "/N$110") (class "Default")
      (node (ref "U8") (pin "11") (pinfunction "DIO4_11") (pintype "bidirectional"))
    )
    (net (code "93") (name "/PWR_IN") (class "Default")
      (node (ref "J1") (pin "PWR") (pinfunction "PWR_PWR") (pintype "bidirectional"))
      (node (ref "JP8") (pin "3") (pinfunction "3_3") (pintype "passive"))
    )
    (net (code "94") (name "/RFIN{slash}OUT") (class "Default")
      (node (ref "C12") (pin "2") (pinfunction "2_2") (pintype "passive"))
      (node (ref "L1") (pin "1") (pinfunction "1_1") (pintype "passive"))
      (node (ref "U6") (pin "18") (pinfunction "RFIN/OUT_18") (pintype "bidirectional"))
    )
    (net (code "95") (name "/RF_50") (class "Default")
      (node (ref "U12") (pin "P$3") (pinfunction "SIGNAL_P$3") (pintype "bidirectional"))
      (node (ref "U5") (pin "6") (pinfunction "6_6") (pintype "passive"))
    )
    (net (code "96") (name "/RTC_VBATT") (class "Default")
      (node (ref "BAT") (pin "PWR@2") (pinfunction "+_PWR@2") (pintype "power_in"))
      (node (ref "U9") (pin "3") (pinfunction "VBATT_3") (pintype "bidirectional"))
    )
    (net (code "97") (name "/RTC_X1") (class "Default")
      (node (ref "Q3") (pin "1") (pinfunction "1_1") (pintype "passive"))
      (node (ref "U9") (pin "1") (pinfunction "X1_1") (pintype "bidirectional"))
    )
    (net (code "98") (name "/RTC_X2") (class "Default")
      (node (ref "Q3") (pin "4") (pinfunction "2_4") (pintype "passive"))
      (node (ref "U9") (pin "2") (pinfunction "X2_2") (pintype "bidirectional"))
    )
    (net (code "99") (name "/RVDD") (class "Default")
      (node (ref "U5") (pin "8") (pinfunction "8_8") (pintype "passive"))
    )
    (net (code "100") (name "/RXD") (class "Default")
      (node (ref "SV1") (pin "10") (pinfunction "10_10") (pintype "passive"))
      (node (ref "SV2") (pin "10") (pinfunction "10_10") (pintype "passive"))
      (node (ref "U8") (pin "2") (pinfunction "DOUT_2") (pintype "output"))
    )
    (net (code "101") (name "/RXD_ZWAVE") (class "Default")
      (node (ref "JP3") (pin "2") (pinfunction "2_2") (pintype "passive"))
      (node (ref "U6") (pin "10") (pinfunction "P1.1/ADC3/RXD_10") (pintype "bidirectional"))
    )
    (net (code "102") (name "/SC16_XTAL1") (class "Default")
      (node (ref "C4") (pin "2") (pinfunction "2_2") (pintype "passive"))
      (node (ref "Q1") (pin "P$2") (pinfunction "2_P$2") (pintype "passive"))
      (node (ref "Q2") (pin "3") (pinfunction "3_3") (pintype "passive"))
      (node (ref "U3") (pin "15") (pinfunction "XTAL1_15") (pintype "bidirectional"))
    )
    (net (code "103") (name "/SC16_XTAL2") (class "Default")
      (node (ref "C3") (pin "2") (pinfunction "2_2") (pintype "passive"))
      (node (ref "Q1") (pin "P$1") (pinfunction "1_P$1") (pintype "passive"))
      (node (ref "Q2") (pin "1") (pinfunction "1_1") (pintype "passive"))
      (node (ref "U3") (pin "16") (pinfunction "XTAL2_16") (pintype "bidirectional"))
    )
    (net (code "104") (name "/SC16_~{IRQ}") (class "Default")
      (node (ref "JP10") (pin "1") (pinfunction "1_1") (pintype "passive"))
      (node (ref "R4") (pin "2") (pinfunction "2_2") (pintype "passive"))
      (node (ref "U3") (pin "7") (pinfunction "/IRQ_7") (pintype "bidirectional"))
    )
    (net (code "105") (name "/SCL") (class "Default")
      (node (ref "SV1") (pin "5") (pinfunction "5_5") (pintype "passive"))
      (node (ref "SV2") (pin "5") (pinfunction "5_5") (pintype "passive"))
      (node (ref "U3") (pin "5") (pinfunction "SCL-SCLK_5") (pintype "bidirectional"))
      (node (ref "U7") (pin "1") (pinfunction "SCL_1") (pintype "bidirectional"))
      (node (ref "U9") (pin "6") (pinfunction "SCL_6") (pintype "bidirectional"))
    )
    (net (code "106") (name "/SCLK") (class "Default")
      (node (ref "SV1") (pin "23") (pinfunction "23_23") (pintype "passive"))
      (node (ref "SV2") (pin "23") (pinfunction "23_23") (pintype "passive"))
      (node (ref "U1") (pin "13") (pinfunction "P1_5/SCK_13") (pintype "bidirectional"))
      (node (ref "U2") (pin "13") (pinfunction "P1_5/SCK_13") (pintype "bidirectional"))
      (node (ref "U4") (pin "13") (pinfunction "SCK_13") (pintype "bidirectional"))
      (node (ref "U6") (pin "8") (pinfunction "P1.4/SCK_8") (pintype "bidirectional"))
    )
    (net (code "107") (name "/SDA") (class "Default")
      (node (ref "SV1") (pin "3") (pinfunction "3_3") (pintype "passive"))
      (node (ref "SV2") (pin "3") (pinfunction "3_3") (pintype "passive"))
      (node (ref "U3") (pin "6") (pinfunction "SDA-VSS_6") (pintype "bidirectional"))
      (node (ref "U7") (pin "6") (pinfunction "SDA_6") (pintype "bidirectional"))
      (node (ref "U9") (pin "5") (pinfunction "SDA_5") (pintype "bidirectional"))
    )
    (net (code "108") (name "/SPI_0") (class "Default")
      (node (ref "SV1") (pin "24") (pinfunction "24_24") (pintype "passive"))
      (node (ref "SV2") (pin "24") (pinfunction "24_24") (pintype "passive"))
      (node (ref "U1") (pin "14") (pinfunction "P1_4/SS_14") (pintype "bidirectional"))
    )
    (net (code "109") (name "/SPI_1") (class "Default")
      (node (ref "SV1") (pin "26") (pinfunction "26_26") (pintype "passive"))
      (node (ref "SV2") (pin "26") (pinfunction "26_26") (pintype "passive"))
    )
    (net (code "110") (name "/TXD") (class "Default")
      (node (ref "SV1") (pin "8") (pinfunction "8_8") (pintype "passive"))
      (node (ref "SV2") (pin "8") (pinfunction "8_8") (pintype "passive"))
      (node (ref "U8") (pin "3") (pinfunction "DIN_3") (pintype "input"))
    )
    (net (code "111") (name "/TXD_ZWAVE") (class "Default")
      (node (ref "JP3") (pin "1") (pinfunction "1_1") (pintype "passive"))
      (node (ref "U6") (pin "15") (pinfunction "P1.0/ADC/TXD_15") (pintype "bidirectional"))
    )
    (net (code "112") (name "/TX_433") (class "Default")
      (node (ref "JP2") (pin "1") (pinfunction "1_1") (pintype "passive"))
      (node (ref "U2") (pin "3") (pinfunction "P0_3/TX_3") (pintype "bidirectional"))
    )
    (net (code "113") (name "/TX_868") (class "Default")
      (node (ref "JP1") (pin "1") (pinfunction "1_1") (pintype "passive"))
      (node (ref "U1") (pin "3") (pinfunction "P0_3/TX_3") (pintype "bidirectional"))
    )
    (net (code "114") (name "/VDD") (class "Default")
      (node (ref "U3") (pin "8") (pinfunction "I2C-/SPI_8") (pintype "bidirectional"))
    )
    (net (code "115") (name "/~{IRQ_RFM12}") (class "Default")
      (node (ref "JP6") (pin "1") (pinfunction "1_1") (pintype "passive"))
      (node (ref "U4") (pin "2") (pinfunction "NIRQ_2") (pintype "bidirectional"))
    )
    (net (code "116") (name "/~{RESET_433}") (class "Default")
      (node (ref "TP2") (pin "TP") (pinfunction "TP_TP") (pintype "input"))
      (node (ref "U2") (pin "15") (pinfunction "~{RESET}_15") (pintype "input"))
    )
    (net (code "117") (name "/~{RESET_868}") (class "Default")
      (node (ref "TP8") (pin "TP") (pinfunction "TP_TP") (pintype "input"))
      (node (ref "U1") (pin "15") (pinfunction "~{RESET}_15") (pintype "input"))
    )
    (net (code "118") (name "/~{SERIAL_EN_433}") (class "Default")
      (node (ref "TP13") (pin "TP") (pinfunction "TP_TP") (pintype "input"))
      (node (ref "U2") (pin "17") (pinfunction "P0_1_17") (pintype "bidirectional"))
    )
    (net (code "119") (name "/~{SERIAL_EN_868}") (class "Default")
      (node (ref "JP5") (pin "1") (pinfunction "1_1") (pintype "passive"))
      (node (ref "TP12") (pin "TP") (pinfunction "TP_TP") (pintype "input"))
      (node (ref "U1") (pin "17") (pinfunction "P0_1_17") (pintype "bidirectional"))
    )
    (net (code "120") (name "/~{SS_433}") (class "Default")
      (node (ref "JP11") (pin "2") (pinfunction "2_2") (pintype "passive"))
      (node (ref "U2") (pin "14") (pinfunction "P1_4/SS_14") (pintype "bidirectional"))
    )
    (net (code "121") (name "/~{SS_RFM12}") (class "Default")
      (node (ref "JP11") (pin "1") (pinfunction "1_1") (pintype "passive"))
      (node (ref "U4") (pin "14") (pinfunction "NSEL_14") (pintype "bidirectional"))
    )
    (net (code "122") (name "/~{SS_ZWAVE}") (class "Default")
      (node (ref "JP11") (pin "3") (pinfunction "3_3") (pintype "passive"))
      (node (ref "U6") (pin "5") (pinfunction "P1.5_5") (pintype "bidirectional"))
    )
    (net (code "123") (name "Net-(U10-IN)") (class "Default")
      (node (ref "C8") (pin "1") (pinfunction "1_1") (pintype "passive"))
      (node (ref "JP8") (pin "2") (pinfunction "2_2") (pintype "passive"))
      (node (ref "U10") (pin "3") (pinfunction "IN_3") (pintype "input"))
    )
    (net (code "124") (name "Net-(U15-SIGNAL)") (class "Default")
      (node (ref "C13") (pin "2") (pinfunction "2_2") (pintype "passive"))
      (node (ref "L1") (pin "2") (pinfunction "2_2") (pintype "passive"))
      (node (ref "TP11") (pin "TP") (pinfunction "TP_TP") (pintype "input"))
      (node (ref "U15") (pin "P$3") (pinfunction "SIGNAL_P$3") (pintype "bidirectional"))
    )
  )
)
